# v1.net
KiCad netlist of a schematic drawn in EAGLE
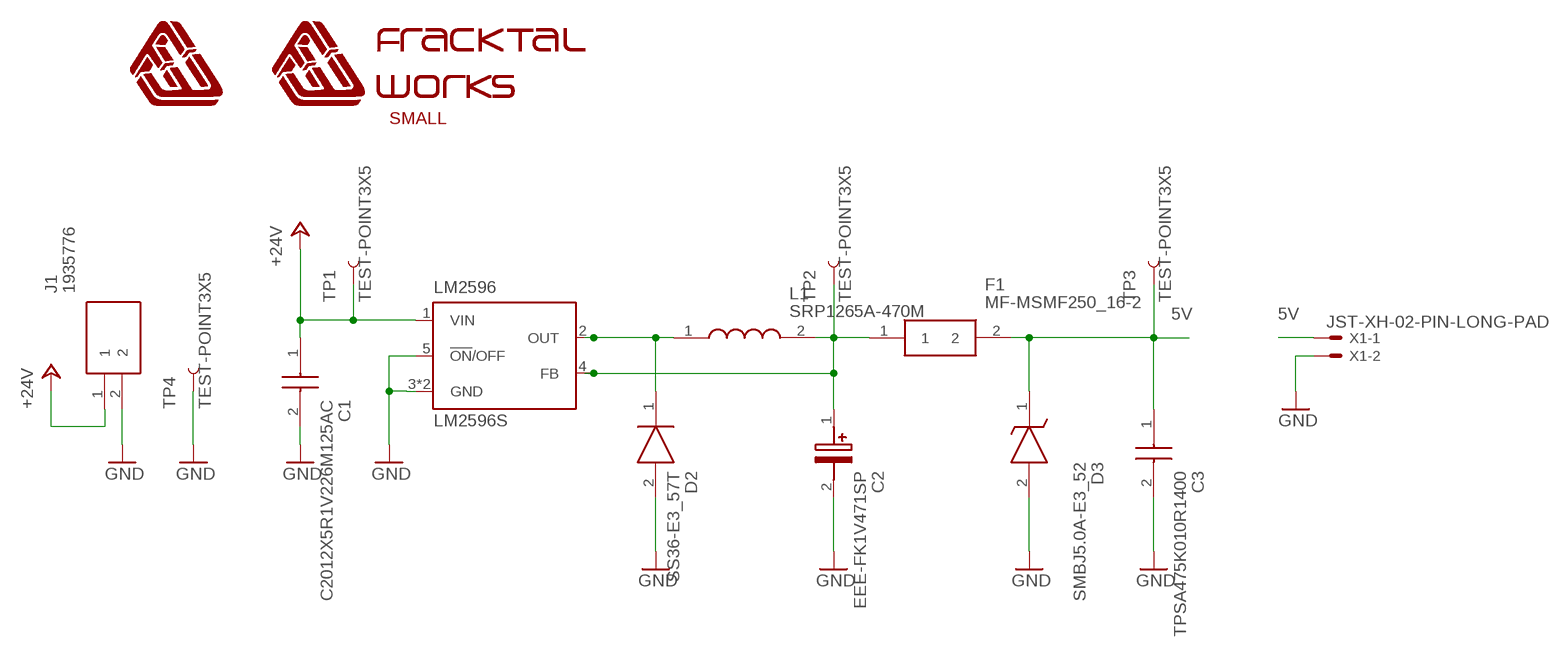
[diagram p0: schematic, sheet 1]

(export (version "E")
  (design (tool "Eeschema 10.0.6"))
  (components
    (comp (ref "C1")
      (value "C2012X5R1V226M125AC")
      (footprint "eagle-import:CAPC2012X145N")
      (fields
        (field (name "MOUSER_PART_NUMBER") "810-C2012X5R1V226MAC")
        (field (name "RS_PART_NUMBER") "9159334P")
      )
      (libsource (lib "eagle-import") (part "C2012X5R1V226M125AC"))
    )
    (comp (ref "C2")
      (value "EEE-FK1V471SP")
      (footprint "eagle-import:CAPAE1030X1050N")
      (fields (field (name "MOUSER_PART_NUMBER") "667-EEE-FK1V471SP"))
      (libsource (lib "eagle-import") (part "EEE-FK1V471SP"))
    )
    (comp (ref "C3")
      (value "TPSA475K010R1400")
      (footprint "eagle-import:CAPPM3216X180N")
      (fields
        (field (name "MOUSER_PART_NUMBER") "581-TPSA475K010R1400")
        (field (name "RS_PART_NUMBER") "1366129")
      )
      (libsource (lib "eagle-import") (part "TPSA475K010R1400"))
    )
    (comp (ref "D2")
      (value "SS36-E3_57T")
      (footprint "eagle-import:DIOM7959X262N")
      (fields
        (field (name "MANUFACTURER_PART_NUMBER") "SS36-E3/57T")
        (field (name "MOUSER_PART_NUMBER") "625-SS36-E3")
        (field (name "RS_PART_NUMBER") "7000975P")
      )
      (libsource (lib "eagle-import") (part "SS36-E3_57T"))
    )
    (comp (ref "D3")
      (value "SMBJ5.0A-E3_52")
      (footprint "eagle-import:DIOM5436X244N")
      (fields
        (field (name "MANUFACTURER_PART_NUMBER") "SMBJ5.0A-E3/52")
        (field (name "MOUSER_PART_NUMBER") "625-SMBJ5.0A-E3")
        (field (name "RS_PART_NUMBER") "1652507")
      )
      (libsource (lib "eagle-import") (part "SMBJ5.0A-E3_52"))
    )
    (comp (ref "F1")
      (value "MF-MSMF250_16-2")
      (footprint "eagle-import:FUSC4632X160N")
      (fields
        (field (name "MANUFACTURER_PART_NUMBER") "MF-MSMF250/16-2")
        (field (name "MOUSER_PART_NUMBER") "652-MF-MSMF250/16-2")
        (field (name "RS_PART_NUMBER") "6478229P")
      )
      (libsource (lib "eagle-import") (part "MF-MSMF250_16-2"))
    )
    (comp (ref "J1")
      (value "1935776")
      (footprint "eagle-import:SHDR2W110P0X500_1X2_1000X900X1")
      (fields (field (name "MOUSER_PART_NUMBER") "651-1935776") (field (name "RS_PART_NUMBER") "5487272"))
      (libsource (lib "eagle-import") (part "1935776"))
    )
    (comp (ref "L1")
      (value "SRP1265A-470M")
      (footprint "eagle-import:SRP1265A")
      (fields
        (field (name "MOUSER_PART_NUMBER") "652-SRP1265A-470M")
        (field (name "RS_PART_NUMBER") "8193513P")
      )
      (libsource (lib "eagle-import") (part "SRP1265A-470M"))
    )
    (comp (ref "LM2596")
      (value "LM2596S")
      (footprint "eagle-import:LM2596_TO263-5")
      (fields (field (name "MF") "NATIONAL SEMICONDUCTOR") (field (name "MPN") "LM2596S-ADJ/NOPB"))
      (libsource (lib "eagle-import") (part "LM2596S"))
    )
    (comp (ref "TP1")
      (value "TEST-POINT3X5")
      (footprint "eagle-import:PAD.03X.05")
      (libsource (lib "eagle-import") (part "TEST-POINT3X5"))
    )
    (comp (ref "TP2")
      (value "TEST-POINT3X5")
      (footprint "eagle-import:PAD.03X.05")
      (libsource (lib "eagle-import") (part "TEST-POINT3X5"))
    )
    (comp (ref "TP3")
      (value "TEST-POINT3X5")
      (footprint "eagle-import:PAD.03X.05")
      (libsource (lib "eagle-import") (part "TEST-POINT3X5"))
    )
    (comp (ref "TP4")
      (value "TEST-POINT3X5")
      (footprint "eagle-import:PAD.03X.05")
      (libsource (lib "eagle-import") (part "TEST-POINT3X5"))
    )
    (comp (ref "U$1")
      (value "FWLOGO")
      (footprint "eagle-import:FWLOGO")
      (libsource (lib "eagle-import") (part "FWLOGO"))
    )
    (comp (ref "U$2")
      (value "FWLOGO_TEXT_SMALL")
      (footprint "eagle-import:FWLOGO_TEXT_SMALL")
      (libsource (lib "eagle-import") (part "FWLOGO_TEXT_SMALL"))
    )
    (comp (ref "X1")
      (value "JST-XH-02-PIN-LONG-PAD")
      (footprint "eagle-import:JST-XH-02-PACKAGE-LONG-PAD")
      (libsource (lib "eagle-import") (part "JST-XH-02-PIN-LONG-PAD"))
    )
  )
  (nets
    (net (code "1") (name "+24V") (class "Default")
      (node (ref "C1") (pin "1") (pinfunction "1_1") (pintype "bidirectional"))
      (node (ref "J1") (pin "1") (pinfunction "1_1") (pintype "bidirectional"))
      (node (ref "LM2596") (pin "1") (pinfunction "VIN_1") (pintype "input"))
      (node (ref "TP1") (pin "P$1") (pinfunction "1_P$1") (pintype "bidirectional"))
    )
    (net (code "2") (name "/5V") (class "Default")
      (node (ref "C3") (pin "1") (pinfunction "1_1") (pintype "bidirectional"))
      (node (ref "D3") (pin "1") (pinfunction "K_1") (pintype "bidirectional"))
      (node (ref "F1") (pin "2") (pinfunction "2_2") (pintype "bidirectional"))
      (node (ref "TP3") (pin "P$1") (pinfunction "1_P$1") (pintype "bidirectional"))
      (node (ref "X1") (pin "1") (pinfunction "S_1") (pintype "passive"))
    )
    (net (code "3") (name "GND") (class "Default")
      (node (ref "C1") (pin "2") (pinfunction "2_2") (pintype "bidirectional"))
      (node (ref "C2") (pin "2") (pinfunction "-_2") (pintype "bidirectional"))
      (node (ref "C3") (pin "2") (pinfunction "2_2") (pintype "bidirectional"))
      (node (ref "D2") (pin "2") (pinfunction "A_2") (pintype "bidirectional"))
      (node (ref "D3") (pin "2") (pinfunction "A_2") (pintype "bidirectional"))
      (node (ref "J1") (pin "2") (pinfunction "2_2") (pintype "bidirectional"))
      (node (ref "LM2596") (pin "3") (pinfunction "GND_3") (pintype "power_in"))
      (node (ref "LM2596") (pin "5") (pinfunction "~{ON}/OFF_5") (pintype "input"))
      (node (ref "LM2596") (pin "6") (pinfunction "GND_6") (pintype "power_in"))
      (node (ref "TP4") (pin "P$1") (pinfunction "1_P$1") (pintype "bidirectional"))
      (node (ref "X1") (pin "2") (pinfunction "S_2") (pintype "passive"))
    )
    (net (code "4") (name "Net-(C2-+)") (class "Default")
      (node (ref "C2") (pin "1") (pinfunction "+_1") (pintype "bidirectional"))
      (node (ref "F1") (pin "1") (pinfunction "1_1") (pintype "bidirectional"))
      (node (ref "L1") (pin "2") (pinfunction "2_2") (pintype "bidirectional"))
      (node (ref "LM2596") (pin "4") (pinfunction "FB_4") (pintype "input"))
      (node (ref "TP2") (pin "P$1") (pinfunction "1_P$1") (pintype "bidirectional"))
    )
    (net (code "5") (name "Net-(D2-K)") (class "Default")
      (node (ref "D2") (pin "1") (pinfunction "K_1") (pintype "bidirectional"))
      (node (ref "L1") (pin "1") (pinfunction "1_1") (pintype "bidirectional"))
      (node (ref "LM2596") (pin "2") (pinfunction "OUT_2") (pintype "output"))
    )
  )
)
